# JlinkV9_RST.net
KiCad netlist of a schematic drawn in Altium Designer
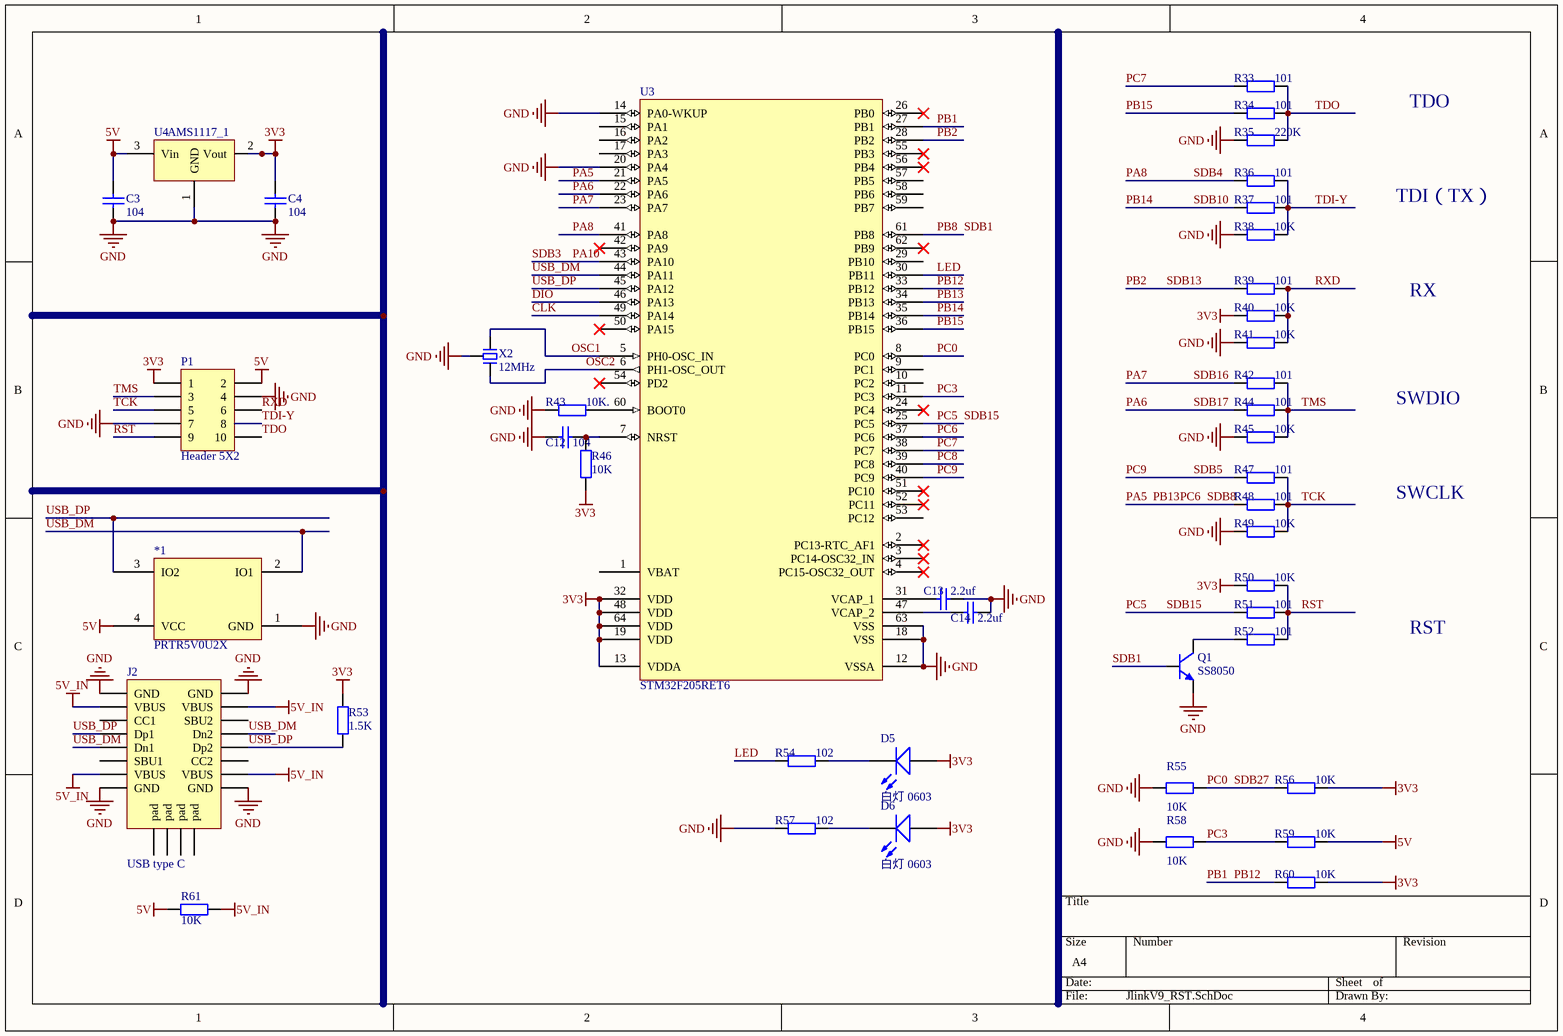
[diagram p0: JlinkV9_RST.SchDoc]

(export (version "E")
  (design (tool "Eeschema 10.0.6"))
  (components
    (comp (ref "*1")
      (value "PRTR5V0U2X")
      (footprint "LC-SOT-143")
      (libsource (lib "XKZ") (part "PRTR5V0U2X"))
    )
    (comp (ref "C3")
      (value "104")
      (footprint "LC-0603_C")
      (description "Polarized Capacitor (Radial)")
      (fields (field (name "PUBLISHER") "Altium Limited"))
      (libsource (lib "Fantasy") (part "Cap"))
    )
    (comp (ref "C4")
      (value "104")
      (footprint "LC-0603_C")
      (description "Polarized Capacitor (Radial)")
      (fields (field (name "PUBLISHER") "Altium Limited"))
      (libsource (lib "Fantasy") (part "Cap"))
    )
    (comp (ref "C12")
      (value "104")
      (footprint "LC-0603_C")
      (description "Polarized Capacitor (Radial)")
      (fields (field (name "PUBLISHER") "Altium Limited"))
      (libsource (lib "Fantasy") (part "Cap"))
    )
    (comp (ref "C13")
      (value "2.2uf")
      (footprint "LC-0603_C")
      (description "Polarized Capacitor (Radial)")
      (fields (field (name "Comment") "2.2UF") (field (name "PUBLISHER") "Altium Limited"))
      (libsource (lib "Fantasy") (part "Cap"))
    )
    (comp (ref "C14")
      (value "2.2uf")
      (footprint "LC-0603_C")
      (description "Polarized Capacitor (Radial)")
      (fields (field (name "Comment") "2.2UF") (field (name "PUBLISHER") "Altium Limited"))
      (libsource (lib "Fantasy") (part "Cap"))
    )
    (comp (ref "D5")
      (value "白灯 0603")
      (footprint "0603_LED_S1")
      (description "发光二极管")
      (libsource (lib "Miscellaneous Devices LC") (part "0603 白灯"))
    )
    (comp (ref "D6")
      (value "白灯 0603")
      (footprint "0603_LED_S1")
      (description "发光二极管")
      (libsource (lib "Miscellaneous Devices LC") (part "0603 白灯"))
    )
    (comp (ref "J2")
      (value "USB type C")
      (footprint "USB Type-C-16Pin_A")
      (libsource (lib "XKZ") (part "USB_C"))
    )
    (comp (ref "P1")
      (value "Header 5X2")
      (footprint "300S-2*5P 2.54MM_2")
      (description "Header, 5-Pin, Dual row")
      (fields (field (name "PUBLISHER") "Altium Limited"))
      (libsource (lib "Miscellaneous Connectors") (part "Header 5X2"))
    )
    (comp (ref "Q1")
      (value "SS8050")
      (footprint "SOT23-3N")
      (description "高频放大-NPN型")
      (fields (field (name "版权归属") "源创客"))
      (libsource (lib "3D库") (part "8050-SMD"))
    )
    (comp (ref "R33")
      (value "101")
      (footprint "LC-0603_R")
      (description "Resistor Chip")
      (fields (field (name "Comment") "100R") (field (name "PUBLISHER") "Altium Limited"))
      (libsource (lib "Fantasy") (part "Resistor"))
    )
    (comp (ref "R34")
      (value "101")
      (footprint "LC-0603_R")
      (description "Resistor Chip")
      (fields (field (name "Comment") "100R") (field (name "PUBLISHER") "Altium Limited"))
      (libsource (lib "Fantasy") (part "Resistor"))
    )
    (comp (ref "R35")
      (value "220K")
      (footprint "LC-0603_R")
      (description "Resistor Chip")
      (fields (field (name "Comment") "10K") (field (name "PUBLISHER") "Altium Limited"))
      (libsource (lib "Fantasy") (part "Resistor"))
    )
    (comp (ref "R36")
      (value "101")
      (footprint "LC-0603_R")
      (description "Resistor Chip")
      (fields (field (name "Comment") "100R") (field (name "PUBLISHER") "Altium Limited"))
      (libsource (lib "Fantasy") (part "Resistor"))
    )
    (comp (ref "R37")
      (value "101")
      (footprint "LC-0603_R")
      (description "Resistor Chip")
      (fields (field (name "Comment") "100R") (field (name "PUBLISHER") "Altium Limited"))
      (libsource (lib "Fantasy") (part "Resistor"))
    )
    (comp (ref "R38")
      (value "10K")
      (footprint "LC-0603_R")
      (description "Resistor Chip")
      (fields (field (name "PUBLISHER") "Altium Limited"))
      (libsource (lib "Fantasy") (part "Resistor"))
    )
    (comp (ref "R39")
      (value "101")
      (footprint "LC-0603_R")
      (description "Resistor Chip")
      (fields (field (name "Comment") "100R") (field (name "PUBLISHER") "Altium Limited"))
      (libsource (lib "Fantasy") (part "Resistor"))
    )
    (comp (ref "R40")
      (value "10K")
      (footprint "LC-0603_R")
      (description "Resistor Chip")
      (fields (field (name "PUBLISHER") "Altium Limited"))
      (libsource (lib "Fantasy") (part "Resistor"))
    )
    (comp (ref "R41")
      (value "10K")
      (footprint "LC-0603_R")
      (description "Resistor Chip")
      (fields (field (name "Comment") "NC") (field (name "PUBLISHER") "Altium Limited"))
      (libsource (lib "Fantasy") (part "Resistor"))
    )
    (comp (ref "R42")
      (value "101")
      (footprint "LC-0603_R")
      (description "Resistor Chip")
      (fields (field (name "Comment") "100R") (field (name "PUBLISHER") "Altium Limited"))
      (libsource (lib "Fantasy") (part "Resistor"))
    )
    (comp (ref "R43")
      (value "10K.")
      (footprint "LC-0603_R")
      (description "Resistor Chip")
      (fields (field (name "Comment") "10K") (field (name "PUBLISHER") "Altium Limited"))
      (libsource (lib "Fantasy") (part "Resistor"))
    )
    (comp (ref "R44")
      (value "101")
      (footprint "LC-0603_R")
      (description "Resistor Chip")
      (fields (field (name "Comment") "100R") (field (name "PUBLISHER") "Altium Limited"))
      (libsource (lib "Fantasy") (part "Resistor"))
    )
    (comp (ref "R45")
      (value "10K")
      (footprint "LC-0603_R")
      (description "Resistor Chip")
      (fields (field (name "PUBLISHER") "Altium Limited"))
      (libsource (lib "Fantasy") (part "Resistor"))
    )
    (comp (ref "R46")
      (value "10K")
      (footprint "LC-0603_R")
      (description "Resistor Chip")
      (fields (field (name "PUBLISHER") "Altium Limited"))
      (libsource (lib "") (part "Resistor_1"))
    )
    (comp (ref "R47")
      (value "101")
      (footprint "LC-0603_R")
      (description "Resistor Chip")
      (fields (field (name "Comment") "100R") (field (name "PUBLISHER") "Altium Limited"))
      (libsource (lib "Fantasy") (part "Resistor"))
    )
    (comp (ref "R48")
      (value "101")
      (footprint "LC-0603_R")
      (description "Resistor Chip")
      (fields (field (name "Comment") "100R") (field (name "PUBLISHER") "Altium Limited"))
      (libsource (lib "Fantasy") (part "Resistor"))
    )
    (comp (ref "R49")
      (value "10K")
      (footprint "LC-0603_R")
      (description "Resistor Chip")
      (fields (field (name "PUBLISHER") "Altium Limited"))
      (libsource (lib "Fantasy") (part "Resistor"))
    )
    (comp (ref "R50")
      (value "10K")
      (footprint "LC-0603_R")
      (description "Resistor Chip")
      (fields (field (name "Comment") "100R") (field (name "PUBLISHER") "Altium Limited"))
      (libsource (lib "Fantasy") (part "Resistor"))
    )
    (comp (ref "R51")
      (value "101")
      (footprint "LC-0603_R")
      (description "Resistor Chip")
      (fields (field (name "Comment") "100R") (field (name "PUBLISHER") "Altium Limited"))
      (libsource (lib "Fantasy") (part "Resistor"))
    )
    (comp (ref "R52")
      (value "101")
      (footprint "LC-0603_R")
      (description "Resistor Chip")
      (fields (field (name "Comment") "100R") (field (name "PUBLISHER") "Altium Limited"))
      (libsource (lib "Fantasy") (part "Resistor"))
    )
    (comp (ref "R53")
      (value "1.5K")
      (footprint "LC-0603_R")
      (description "Resistor")
      (fields (field (name "Comment") "1K") (field (name "PUBLISHER") "Altium Limited"))
      (libsource (lib "") (part "Res2_1"))
    )
    (comp (ref "R54")
      (value "102")
      (footprint "LC-0603_R")
      (description "Resistor Chip")
      (fields (field (name "Comment") "1K") (field (name "PUBLISHER") "Altium Limited"))
      (libsource (lib "Fantasy") (part "Resistor"))
    )
    (comp (ref "R55")
      (value "10K")
      (footprint "LC-0603_R")
      (description "Resistor Chip")
      (fields (field (name "PUBLISHER") "Altium Limited"))
      (libsource (lib "Fantasy") (part "Resistor"))
    )
    (comp (ref "R56")
      (value "10K")
      (footprint "LC-0603_R")
      (description "Resistor Chip")
      (fields (field (name "PUBLISHER") "Altium Limited"))
      (libsource (lib "Fantasy") (part "Resistor"))
    )
    (comp (ref "R57")
      (value "102")
      (footprint "LC-0603_R")
      (description "Resistor Chip")
      (fields (field (name "Comment") "1K") (field (name "PUBLISHER") "Altium Limited"))
      (libsource (lib "Fantasy") (part "Resistor"))
    )
    (comp (ref "R58")
      (value "10K")
      (footprint "LC-0603_R")
      (description "Resistor Chip")
      (fields (field (name "PUBLISHER") "Altium Limited"))
      (libsource (lib "Fantasy") (part "Resistor"))
    )
    (comp (ref "R59")
      (value "10K")
      (footprint "LC-0603_R")
      (description "Resistor Chip")
      (fields (field (name "PUBLISHER") "Altium Limited"))
      (libsource (lib "Fantasy") (part "Resistor"))
    )
    (comp (ref "R60")
      (value "10K")
      (footprint "LC-0603_R")
      (description "Resistor Chip")
      (fields (field (name "PUBLISHER") "Altium Limited"))
      (libsource (lib "Fantasy") (part "Resistor"))
    )
    (comp (ref "R61")
      (value "10K")
      (footprint "LC-0805_R")
      (description "Resistor")
      (fields (field (name "Comment") "1A保险丝") (field (name "PUBLISHER") "Altium Limited"))
      (libsource (lib "XKZ") (part "Res2"))
    )
    (comp (ref "U3")
      (value "STM32F205RET6")
      (footprint "LQFP64 10x10_N")
      (description "Microcontroller   ST")
      (libsource (lib "Fantasy") (part "STM32F205RET6"))
    )
    (comp (ref "U4")
      (value "AMS1117_1")
      (footprint "LC-SOT-223")
      (description "3.3V电压转换器AMS1117")
      (libsource (lib "自创") (part "AMS1117_1"))
    )
    (comp (ref "X2")
      (value "12MHz")
      (footprint "3脚晶振")
      (description "3脚无源晶振")
      (fields (field (name "版权归属") "源创客"))
      (libsource (lib "ATKF405 V1.1") (part "XTAL-3P"))
    )
  )
  (nets
    (net (code "1") (name "/CLK") (class "Default")
      (node (ref "U3") (pin "49") (pinfunction "PA14_49") (pintype "bidirectional"))
    )
    (net (code "2") (name "/DIO") (class "Default")
      (node (ref "U3") (pin "46") (pinfunction "PA13_46") (pintype "bidirectional"))
    )
    (net (code "3") (name "/LED") (class "Default")
      (node (ref "R54") (pin "1") (pinfunction "1_1") (pintype "passive"))
      (node (ref "U3") (pin "30") (pinfunction "PB11_30") (pintype "bidirectional"))
    )
    (net (code "4") (name "/OSC1") (class "Default")
      (node (ref "U3") (pin "5") (pinfunction "PH0-OSC_IN_5") (pintype "input"))
      (node (ref "X2") (pin "1") (pinfunction "1_1") (pintype "passive"))
    )
    (net (code "5") (name "/OSC2") (class "Default")
      (node (ref "U3") (pin "6") (pinfunction "PH1-OSC_OUT_6") (pintype "output"))
      (node (ref "X2") (pin "2") (pinfunction "2_2") (pintype "passive"))
    )
    (net (code "6") (name "/PA5") (class "Default")
      (node (ref "R48") (pin "1") (pinfunction "1_1") (pintype "passive"))
      (node (ref "U3") (pin "21") (pinfunction "PA5_21") (pintype "bidirectional"))
      (node (ref "U3") (pin "34") (pinfunction "PB13_34") (pintype "bidirectional"))
      (node (ref "U3") (pin "37") (pinfunction "PC6_37") (pintype "bidirectional"))
    )
    (net (code "7") (name "/PA6") (class "Default")
      (node (ref "R44") (pin "1") (pinfunction "1_1") (pintype "passive"))
      (node (ref "U3") (pin "22") (pinfunction "PA6_22") (pintype "bidirectional"))
    )
    (net (code "8") (name "/PA7") (class "Default")
      (node (ref "R42") (pin "1") (pinfunction "1_1") (pintype "passive"))
      (node (ref "U3") (pin "23") (pinfunction "PA7_23") (pintype "bidirectional"))
    )
    (net (code "9") (name "/PA8") (class "Default")
      (node (ref "R36") (pin "1") (pinfunction "1_1") (pintype "passive"))
      (node (ref "U3") (pin "41") (pinfunction "PA8_41") (pintype "bidirectional"))
    )
    (net (code "10") (name "/PA10") (class "Default")
      (node (ref "U3") (pin "43") (pinfunction "PA10_43") (pintype "bidirectional"))
    )
    (net (code "11") (name "/PB1") (class "Default")
      (node (ref "R60") (pin "1") (pinfunction "1_1") (pintype "passive"))
      (node (ref "U3") (pin "27") (pinfunction "PB1_27") (pintype "bidirectional"))
      (node (ref "U3") (pin "33") (pinfunction "PB12_33") (pintype "bidirectional"))
    )
    (net (code "12") (name "/PB2") (class "Default")
      (node (ref "R39") (pin "1") (pinfunction "1_1") (pintype "passive"))
      (node (ref "U3") (pin "28") (pinfunction "PB2_28") (pintype "bidirectional"))
    )
    (net (code "13") (name "/PB8") (class "Default")
      (node (ref "Q1") (pin "1") (pinfunction "B_1") (pintype "passive"))
      (node (ref "U3") (pin "61") (pinfunction "PB8_61") (pintype "bidirectional"))
    )
    (net (code "14") (name "/PB14") (class "Default")
      (node (ref "R37") (pin "1") (pinfunction "1_1") (pintype "passive"))
      (node (ref "U3") (pin "35") (pinfunction "PB14_35") (pintype "bidirectional"))
    )
    (net (code "15") (name "/PB15") (class "Default")
      (node (ref "R34") (pin "1") (pinfunction "1_1") (pintype "passive"))
      (node (ref "U3") (pin "36") (pinfunction "PB15_36") (pintype "bidirectional"))
    )
    (net (code "16") (name "/PC0") (class "Default")
      (node (ref "R55") (pin "2") (pinfunction "2_2") (pintype "passive"))
      (node (ref "R56") (pin "1") (pinfunction "1_1") (pintype "passive"))
      (node (ref "U3") (pin "8") (pinfunction "PC0_8") (pintype "bidirectional"))
    )
    (net (code "17") (name "/PC3") (class "Default")
      (node (ref "R58") (pin "2") (pinfunction "2_2") (pintype "passive"))
      (node (ref "R59") (pin "1") (pinfunction "1_1") (pintype "passive"))
      (node (ref "U3") (pin "11") (pinfunction "PC3_11") (pintype "bidirectional"))
    )
    (net (code "18") (name "/PC5") (class "Default")
      (node (ref "R51") (pin "1") (pinfunction "1_1") (pintype "passive"))
      (node (ref "U3") (pin "25") (pinfunction "PC5_25") (pintype "bidirectional"))
    )
    (net (code "19") (name "/PC7") (class "Default")
      (node (ref "R33") (pin "1") (pinfunction "1_1") (pintype "passive"))
      (node (ref "U3") (pin "38") (pinfunction "PC7_38") (pintype "bidirectional"))
    )
    (net (code "20") (name "/PC8") (class "Default")
      (node (ref "U3") (pin "39") (pinfunction "PC8_39") (pintype "bidirectional"))
    )
    (net (code "21") (name "/PC9") (class "Default")
      (node (ref "R47") (pin "1") (pinfunction "1_1") (pintype "passive"))
      (node (ref "U3") (pin "40") (pinfunction "PC9_40") (pintype "bidirectional"))
    )
    (net (code "22") (name "/RST") (class "Default")
      (node (ref "P1") (pin "9") (pinfunction "9_9") (pintype "passive"))
      (node (ref "R50") (pin "2") (pinfunction "2_2") (pintype "passive"))
      (node (ref "R51") (pin "2") (pinfunction "2_2") (pintype "passive"))
      (node (ref "R52") (pin "2") (pinfunction "2_2") (pintype "passive"))
    )
    (net (code "23") (name "/RXD") (class "Default")
      (node (ref "P1") (pin "6") (pinfunction "6_6") (pintype "passive"))
      (node (ref "R39") (pin "2") (pinfunction "2_2") (pintype "passive"))
      (node (ref "R40") (pin "2") (pinfunction "2_2") (pintype "passive"))
      (node (ref "R41") (pin "2") (pinfunction "2_2") (pintype "passive"))
    )
    (net (code "24") (name "/TCK") (class "Default")
      (node (ref "P1") (pin "5") (pinfunction "5_5") (pintype "passive"))
      (node (ref "R47") (pin "2") (pinfunction "2_2") (pintype "passive"))
      (node (ref "R48") (pin "2") (pinfunction "2_2") (pintype "passive"))
      (node (ref "R49") (pin "2") (pinfunction "2_2") (pintype "passive"))
    )
    (net (code "25") (name "/TDI-Y") (class "Default")
      (node (ref "P1") (pin "8") (pinfunction "8_8") (pintype "passive"))
      (node (ref "R36") (pin "2") (pinfunction "2_2") (pintype "passive"))
      (node (ref "R37") (pin "2") (pinfunction "2_2") (pintype "passive"))
      (node (ref "R38") (pin "2") (pinfunction "2_2") (pintype "passive"))
    )
    (net (code "26") (name "/TDO") (class "Default")
      (node (ref "P1") (pin "10") (pinfunction "10_10") (pintype "passive"))
      (node (ref "R33") (pin "2") (pinfunction "2_2") (pintype "passive"))
      (node (ref "R34") (pin "2") (pinfunction "2_2") (pintype "passive"))
      (node (ref "R35") (pin "2") (pinfunction "2_2") (pintype "passive"))
    )
    (net (code "27") (name "/TMS") (class "Default")
      (node (ref "P1") (pin "3") (pinfunction "3_3") (pintype "passive"))
      (node (ref "R42") (pin "2") (pinfunction "2_2") (pintype "passive"))
      (node (ref "R44") (pin "2") (pinfunction "2_2") (pintype "passive"))
      (node (ref "R45") (pin "2") (pinfunction "2_2") (pintype "passive"))
    )
    (net (code "28") (name "/USB_DM") (class "Default")
      (node (ref "*1") (pin "2") (pinfunction "IO1_2") (pintype "passive"))
      (node (ref "J2") (pin "A7") (pinfunction "Dn1_A7") (pintype "passive"))
      (node (ref "J2") (pin "B7") (pinfunction "Dn2_B7") (pintype "passive"))
      (node (ref "U3") (pin "44") (pinfunction "PA11_44") (pintype "bidirectional"))
    )
    (net (code "29") (name "/USB_DP") (class "Default")
      (node (ref "*1") (pin "3") (pinfunction "IO2_3") (pintype "passive"))
      (node (ref "J2") (pin "A6") (pinfunction "Dp1_A6") (pintype "passive"))
      (node (ref "J2") (pin "B6") (pinfunction "Dp2_B6") (pintype "passive"))
      (node (ref "R53") (pin "2") (pinfunction "2_2") (pintype "passive"))
      (node (ref "U3") (pin "45") (pinfunction "PA12_45") (pintype "bidirectional"))
    )
    (net (code "30") (name "3V3") (class "Default")
      (node (ref "C4") (pin "2") (pinfunction "2_2") (pintype "passive"))
      (node (ref "D5") (pin "A") (pinfunction "A_A") (pintype "passive"))
      (node (ref "D6") (pin "A") (pinfunction "A_A") (pintype "passive"))
      (node (ref "P1") (pin "1") (pinfunction "1_1") (pintype "passive"))
      (node (ref "R40") (pin "1") (pinfunction "1_1") (pintype "passive"))
      (node (ref "R46") (pin "1") (pinfunction "1_1") (pintype "passive"))
      (node (ref "R50") (pin "1") (pinfunction "1_1") (pintype "passive"))
      (node (ref "R53") (pin "1") (pinfunction "1_1") (pintype "passive"))
      (node (ref "R56") (pin "2") (pinfunction "2_2") (pintype "passive"))
      (node (ref "R60") (pin "2") (pinfunction "2_2") (pintype "passive"))
      (node (ref "U3") (pin "13") (pinfunction "VDDA_13") (pintype "power_in"))
      (node (ref "U3") (pin "19") (pinfunction "VDD_19") (pintype "power_in"))
      (node (ref "U3") (pin "32") (pinfunction "VDD_32") (pintype "power_in"))
      (node (ref "U3") (pin "48") (pinfunction "VDD_48") (pintype "power_in"))
      (node (ref "U3") (pin "64") (pinfunction "VDD_64") (pintype "power_in"))
      (node (ref "U4") (pin "2") (pinfunction "Vout_2") (pintype "passive"))
    )
    (net (code "31") (name "5V") (class "Default")
      (node (ref "*1") (pin "4") (pinfunction "VCC_4") (pintype "passive"))
      (node (ref "C3") (pin "2") (pinfunction "2_2") (pintype "passive"))
      (node (ref "P1") (pin "2") (pinfunction "2_2") (pintype "passive"))
      (node (ref "R59") (pin "2") (pinfunction "2_2") (pintype "passive"))
      (node (ref "R61") (pin "1") (pinfunction "1_1") (pintype "passive"))
      (node (ref "U4") (pin "3") (pinfunction "Vin_3") (pintype "passive"))
    )
    (net (code "32") (name "5V_IN") (class "Default")
      (node (ref "J2") (pin "A4") (pinfunction "VBUS_A4") (pintype "passive"))
      (node (ref "J2") (pin "A9") (pinfunction "VBUS_A9") (pintype "passive"))
      (node (ref "J2") (pin "B4") (pinfunction "VBUS_B4") (pintype "passive"))
      (node (ref "J2") (pin "B9") (pinfunction "VBUS_B9") (pintype "passive"))
      (node (ref "R61") (pin "2") (pinfunction "2_2") (pintype "passive"))
    )
    (net (code "33") (name "GND") (class "Default")
      (node (ref "*1") (pin "1") (pinfunction "GND_1") (pintype "passive"))
      (node (ref "C12") (pin "2") (pinfunction "2_2") (pintype "passive"))
      (node (ref "C13") (pin "1") (pinfunction "1_1") (pintype "passive"))
      (node (ref "C14") (pin "1") (pinfunction "1_1") (pintype "passive"))
      (node (ref "C3") (pin "1") (pinfunction "1_1") (pintype "passive"))
      (node (ref "C4") (pin "1") (pinfunction "1_1") (pintype "passive"))
      (node (ref "J2") (pin "A1") (pinfunction "GND_A1") (pintype "passive"))
      (node (ref "J2") (pin "A12") (pinfunction "GND_A12") (pintype "passive"))
      (node (ref "J2") (pin "B1") (pinfunction "GND_B1") (pintype "passive"))
      (node (ref "J2") (pin "B12") (pinfunction "GND_B12") (pintype "passive"))
      (node (ref "P1") (pin "4") (pinfunction "4_4") (pintype "passive"))
      (node (ref "P1") (pin "7") (pinfunction "7_7") (pintype "passive"))
      (node (ref "Q1") (pin "2") (pinfunction "E_2") (pintype "passive"))
      (node (ref "R35") (pin "1") (pinfunction "1_1") (pintype "passive"))
      (node (ref "R38") (pin "1") (pinfunction "1_1") (pintype "passive"))
      (node (ref "R41") (pin "1") (pinfunction "1_1") (pintype "passive"))
      (node (ref "R43") (pin "1") (pinfunction "1_1") (pintype "passive"))
      (node (ref "R45") (pin "1") (pinfunction "1_1") (pintype "passive"))
      (node (ref "R49") (pin "1") (pinfunction "1_1") (pintype "passive"))
      (node (ref "R55") (pin "1") (pinfunction "1_1") (pintype "passive"))
      (node (ref "R57") (pin "1") (pinfunction "1_1") (pintype "passive"))
      (node (ref "R58") (pin "1") (pinfunction "1_1") (pintype "passive"))
      (node (ref "U3") (pin "12") (pinfunction "VSSA_12") (pintype "power_in"))
      (node (ref "U3") (pin "14") (pinfunction "PA0-WKUP_14") (pintype "bidirectional"))
      (node (ref "U3") (pin "18") (pinfunction "VSS_18") (pintype "power_in"))
      (node (ref "U3") (pin "20") (pinfunction "PA4_20") (pintype "bidirectional"))
      (node (ref "U3") (pin "63") (pinfunction "VSS_63") (pintype "power_in"))
      (node (ref "U4") (pin "1") (pinfunction "GND_1") (pintype "passive"))
      (node (ref "X2") (pin "3") (pinfunction "3_3") (pintype "passive"))
    )
    (net (code "34") (name "Net-(D5-PadK)") (class "Default")
      (node (ref "D5") (pin "K") (pinfunction "K_K") (pintype "passive"))
      (node (ref "R54") (pin "2") (pinfunction "2_2") (pintype "passive"))
    )
    (net (code "35") (name "Net-(D6-PadK)") (class "Default")
      (node (ref "D6") (pin "K") (pinfunction "K_K") (pintype "passive"))
      (node (ref "R57") (pin "2") (pinfunction "2_2") (pintype "passive"))
    )
    (net (code "36") (name "Net-(Q1-C)") (class "Default")
      (node (ref "Q1") (pin "3") (pinfunction "C_3") (pintype "passive"))
      (node (ref "R52") (pin "1") (pinfunction "1_1") (pintype "passive"))
    )
    (net (code "37") (name "Net-(U3-BOOT0)") (class "Default")
      (node (ref "R43") (pin "2") (pinfunction "2_2") (pintype "passive"))
      (node (ref "U3") (pin "60") (pinfunction "BOOT0_60") (pintype "input"))
    )
    (net (code "38") (name "Net-(U3-NRST)") (class "Default")
      (node (ref "C12") (pin "1") (pinfunction "1_1") (pintype "passive"))
      (node (ref "R46") (pin "2") (pinfunction "2_2") (pintype "passive"))
      (node (ref "U3") (pin "7") (pinfunction "NRST_7") (pintype "bidirectional"))
    )
    (net (code "39") (name "Net-(U3-VCAP_1)") (class "Default")
      (node (ref "C13") (pin "2") (pinfunction "2_2") (pintype "passive"))
      (node (ref "U3") (pin "31") (pinfunction "VCAP_1_31") (pintype "power_in"))
    )
    (net (code "40") (name "Net-(U3-VCAP_2)") (class "Default")
      (node (ref "C14") (pin "2") (pinfunction "2_2") (pintype "passive"))
      (node (ref "U3") (pin "47") (pinfunction "VCAP_2_47") (pintype "power_in"))
    )
    (net (code "41") (name "unconnected-(J2-CC1-PadA5)") (class "Default")
      (node (ref "J2") (pin "A5") (pinfunction "CC1_A5") (pintype "passive"))
    )
    (net (code "42") (name "unconnected-(J2-CC2-PadB5)") (class "Default")
      (node (ref "J2") (pin "B5") (pinfunction "CC2_B5") (pintype "passive"))
    )
    (net (code "43") (name "unconnected-(J2-SBU1-PadA8)") (class "Default")
      (node (ref "J2") (pin "A8") (pinfunction "SBU1_A8") (pintype "passive"))
    )
    (net (code "44") (name "unconnected-(J2-SBU2-PadB8)") (class "Default")
      (node (ref "J2") (pin "B8") (pinfunction "SBU2_B8") (pintype "passive"))
    )
    (net (code "45") (name "unconnected-(J2-pad-Pad0)") (class "Default")
      (node (ref "J2") (pin "0") (pinfunction "pad_0") (pintype "passive"))
    )
    (net (code "46") (name "unconnected-(J2-pad-Pad0)_1") (class "Default")
      (node (ref "J2") (pin "0") (pinfunction "pad_0") (pintype "passive"))
    )
    (net (code "47") (name "unconnected-(J2-pad-Pad0)_2") (class "Default")
      (node (ref "J2") (pin "0") (pinfunction "pad_0") (pintype "passive"))
    )
    (net (code "48") (name "unconnected-(J2-pad-Pad0)_3") (class "Default")
      (node (ref "J2") (pin "0") (pinfunction "pad_0") (pintype "passive"))
    )
    (net (code "49") (name "unconnected-(U3-PA1-Pad15)") (class "Default")
      (node (ref "U3") (pin "15") (pinfunction "PA1_15") (pintype "bidirectional"))
    )
    (net (code "50") (name "unconnected-(U3-PA2-Pad16)") (class "Default")
      (node (ref "U3") (pin "16") (pinfunction "PA2_16") (pintype "bidirectional"))
    )
    (net (code "51") (name "unconnected-(U3-PA3-Pad17)") (class "Default")
      (node (ref "U3") (pin "17") (pinfunction "PA3_17") (pintype "bidirectional"))
    )
    (net (code "52") (name "unconnected-(U3-PA9-Pad42)") (class "Default")
      (node (ref "U3") (pin "42") (pinfunction "PA9_42") (pintype "bidirectional+no_connect"))
    )
    (net (code "53") (name "unconnected-(U3-PA15-Pad50)") (class "Default")
      (node (ref "U3") (pin "50") (pinfunction "PA15_50") (pintype "bidirectional+no_connect"))
    )
    (net (code "54") (name "unconnected-(U3-PB0-Pad26)") (class "Default")
      (node (ref "U3") (pin "26") (pinfunction "PB0_26") (pintype "bidirectional+no_connect"))
    )
    (net (code "55") (name "unconnected-(U3-PB3-Pad55)") (class "Default")
      (node (ref "U3") (pin "55") (pinfunction "PB3_55") (pintype "bidirectional+no_connect"))
    )
    (net (code "56") (name "unconnected-(U3-PB4-Pad56)") (class "Default")
      (node (ref "U3") (pin "56") (pinfunction "PB4_56") (pintype "bidirectional+no_connect"))
    )
    (net (code "57") (name "unconnected-(U3-PB5-Pad57)") (class "Default")
      (node (ref "U3") (pin "57") (pinfunction "PB5_57") (pintype "bidirectional"))
    )
    (net (code "58") (name "unconnected-(U3-PB6-Pad58)") (class "Default")
      (node (ref "U3") (pin "58") (pinfunction "PB6_58") (pintype "bidirectional"))
    )
    (net (code "59") (name "unconnected-(U3-PB7-Pad59)") (class "Default")
      (node (ref "U3") (pin "59") (pinfunction "PB7_59") (pintype "bidirectional"))
    )
    (net (code "60") (name "unconnected-(U3-PB9-Pad62)") (class "Default")
      (node (ref "U3") (pin "62") (pinfunction "PB9_62") (pintype "bidirectional+no_connect"))
    )
    (net (code "61") (name "unconnected-(U3-PB10-Pad29)") (class "Default")
      (node (ref "U3") (pin "29") (pinfunction "PB10_29") (pintype "bidirectional"))
    )
    (net (code "62") (name "unconnected-(U3-PC1-Pad9)") (class "Default")
      (node (ref "U3") (pin "9") (pinfunction "PC1_9") (pintype "bidirectional"))
    )
    (net (code "63") (name "unconnected-(U3-PC2-Pad10)") (class "Default")
      (node (ref "U3") (pin "10") (pinfunction "PC2_10") (pintype "bidirectional"))
    )
    (net (code "64") (name "unconnected-(U3-PC4-Pad24)") (class "Default")
      (node (ref "U3") (pin "24") (pinfunction "PC4_24") (pintype "bidirectional+no_connect"))
    )
    (net (code "65") (name "unconnected-(U3-PC10-Pad51)") (class "Default")
      (node (ref "U3") (pin "51") (pinfunction "PC10_51") (pintype "bidirectional+no_connect"))
    )
    (net (code "66") (name "unconnected-(U3-PC11-Pad52)") (class "Default")
      (node (ref "U3") (pin "52") (pinfunction "PC11_52") (pintype "bidirectional+no_connect"))
    )
    (net (code "67") (name "unconnected-(U3-PC12-Pad53)") (class "Default")
      (node (ref "U3") (pin "53") (pinfunction "PC12_53") (pintype "bidirectional"))
    )
    (net (code "68") (name "unconnected-(U3-PC13-RTC_AF1-Pad2)") (class "Default")
      (node (ref "U3") (pin "2") (pinfunction "PC13-RTC_AF1_2") (pintype "bidirectional+no_connect"))
    )
    (net (code "69") (name "unconnected-(U3-PC14-OSC32_IN-Pad3)") (class "Default")
      (node (ref "U3") (pin "3") (pinfunction "PC14-OSC32_IN_3") (pintype "bidirectional+no_connect"))
    )
    (net (code "70") (name "unconnected-(U3-PC15-OSC32_OUT-Pad4)") (class "Default")
      (node (ref "U3") (pin "4") (pinfunction "PC15-OSC32_OUT_4") (pintype "bidirectional+no_connect"))
    )
    (net (code "71") (name "unconnected-(U3-PD2-Pad54)") (class "Default")
      (node (ref "U3") (pin "54") (pinfunction "PD2_54") (pintype "bidirectional+no_connect"))
    )
    (net (code "72") (name "unconnected-(U3-VBAT-Pad1)") (class "Default")
      (node (ref "U3") (pin "1") (pinfunction "VBAT_1") (pintype "power_in"))
    )
  )
)
